# DSO_Clock.net
KiCad netlist of a schematic drawn in Altium Designer
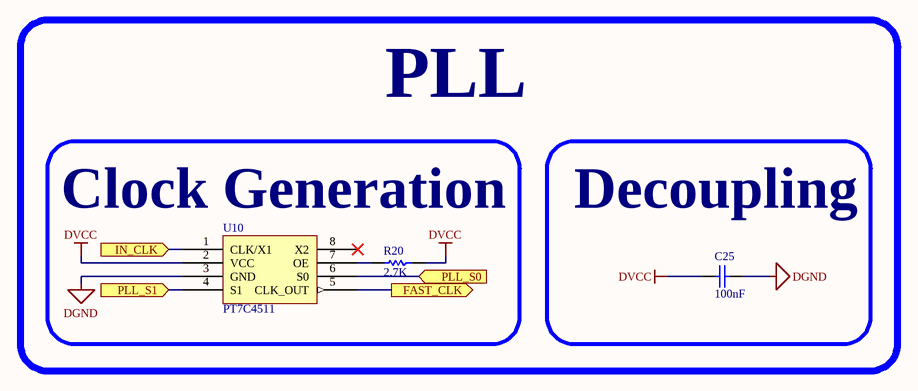
[diagram p0: DSO_Clock.SchDoc]

(export (version "E")
  (design (tool "Eeschema 10.0.6"))
  (components
    (comp (ref "C25")
      (value "100nF")
      (footprint "0805C")
      (description "Capacitor")
      (fields (field (name "REVIEWED BY") "RM - 2018/08/05"))
      (libsource (lib "DSO") (part "C"))
    )
    (comp (ref "R20")
      (value "2.7K")
      (footprint "0805")
      (description "Resistor")
      (fields (field (name "REVIEWED BY") "RM - 2018/08/05"))
      (libsource (lib "DSO") (part "R"))
    )
    (comp (ref "U10")
      (value "PT7C4511")
      (footprint "SOIC-8")
      (description "PLL Clock Multiplier")
      (fields (field (name "REVIEWED BY") "RM - 2018/08/05"))
      (libsource (lib "DSO") (part "PT7C4511"))
    )
  )
  (nets
    (net (code "1") (name "/FAST_CLK") (class "Default")
      (node (ref "U10") (pin "5") (pinfunction "CLK_OUT_5") (pintype "output"))
    )
    (net (code "2") (name "/IN_CLK") (class "Default")
      (node (ref "U10") (pin "1") (pinfunction "CLK/X1_1") (pintype "passive"))
    )
    (net (code "3") (name "/PLL_S0") (class "Default")
      (node (ref "U10") (pin "6") (pinfunction "S0_6") (pintype "passive"))
    )
    (net (code "4") (name "/PLL_S1") (class "Default")
      (node (ref "U10") (pin "4") (pinfunction "S1_4") (pintype "passive"))
    )
    (net (code "5") (name "DGND") (class "Default")
      (node (ref "C25") (pin "1") (pinfunction "1_1") (pintype "passive"))
      (node (ref "U10") (pin "3") (pinfunction "GND_3") (pintype "passive"))
    )
    (net (code "6") (name "DVCC") (class "Default")
      (node (ref "C25") (pin "2") (pinfunction "2_2") (pintype "passive"))
      (node (ref "R20") (pin "1") (pintype "passive"))
      (node (ref "U10") (pin "2") (pinfunction "VCC_2") (pintype "passive"))
    )
    (net (code "7") (name "Net-(U10-OE)") (class "Default")
      (node (ref "R20") (pin "2") (pintype "passive"))
      (node (ref "U10") (pin "7") (pinfunction "OE_7") (pintype "passive"))
    )
    (net (code "8") (name "unconnected-(U10-X2-Pad8)") (class "Default")
      (node (ref "U10") (pin "8") (pinfunction "X2_8") (pintype "passive+no_connect"))
    )
  )
)
